# 5VPS.net
KiCad netlist of a schematic drawn in EAGLE
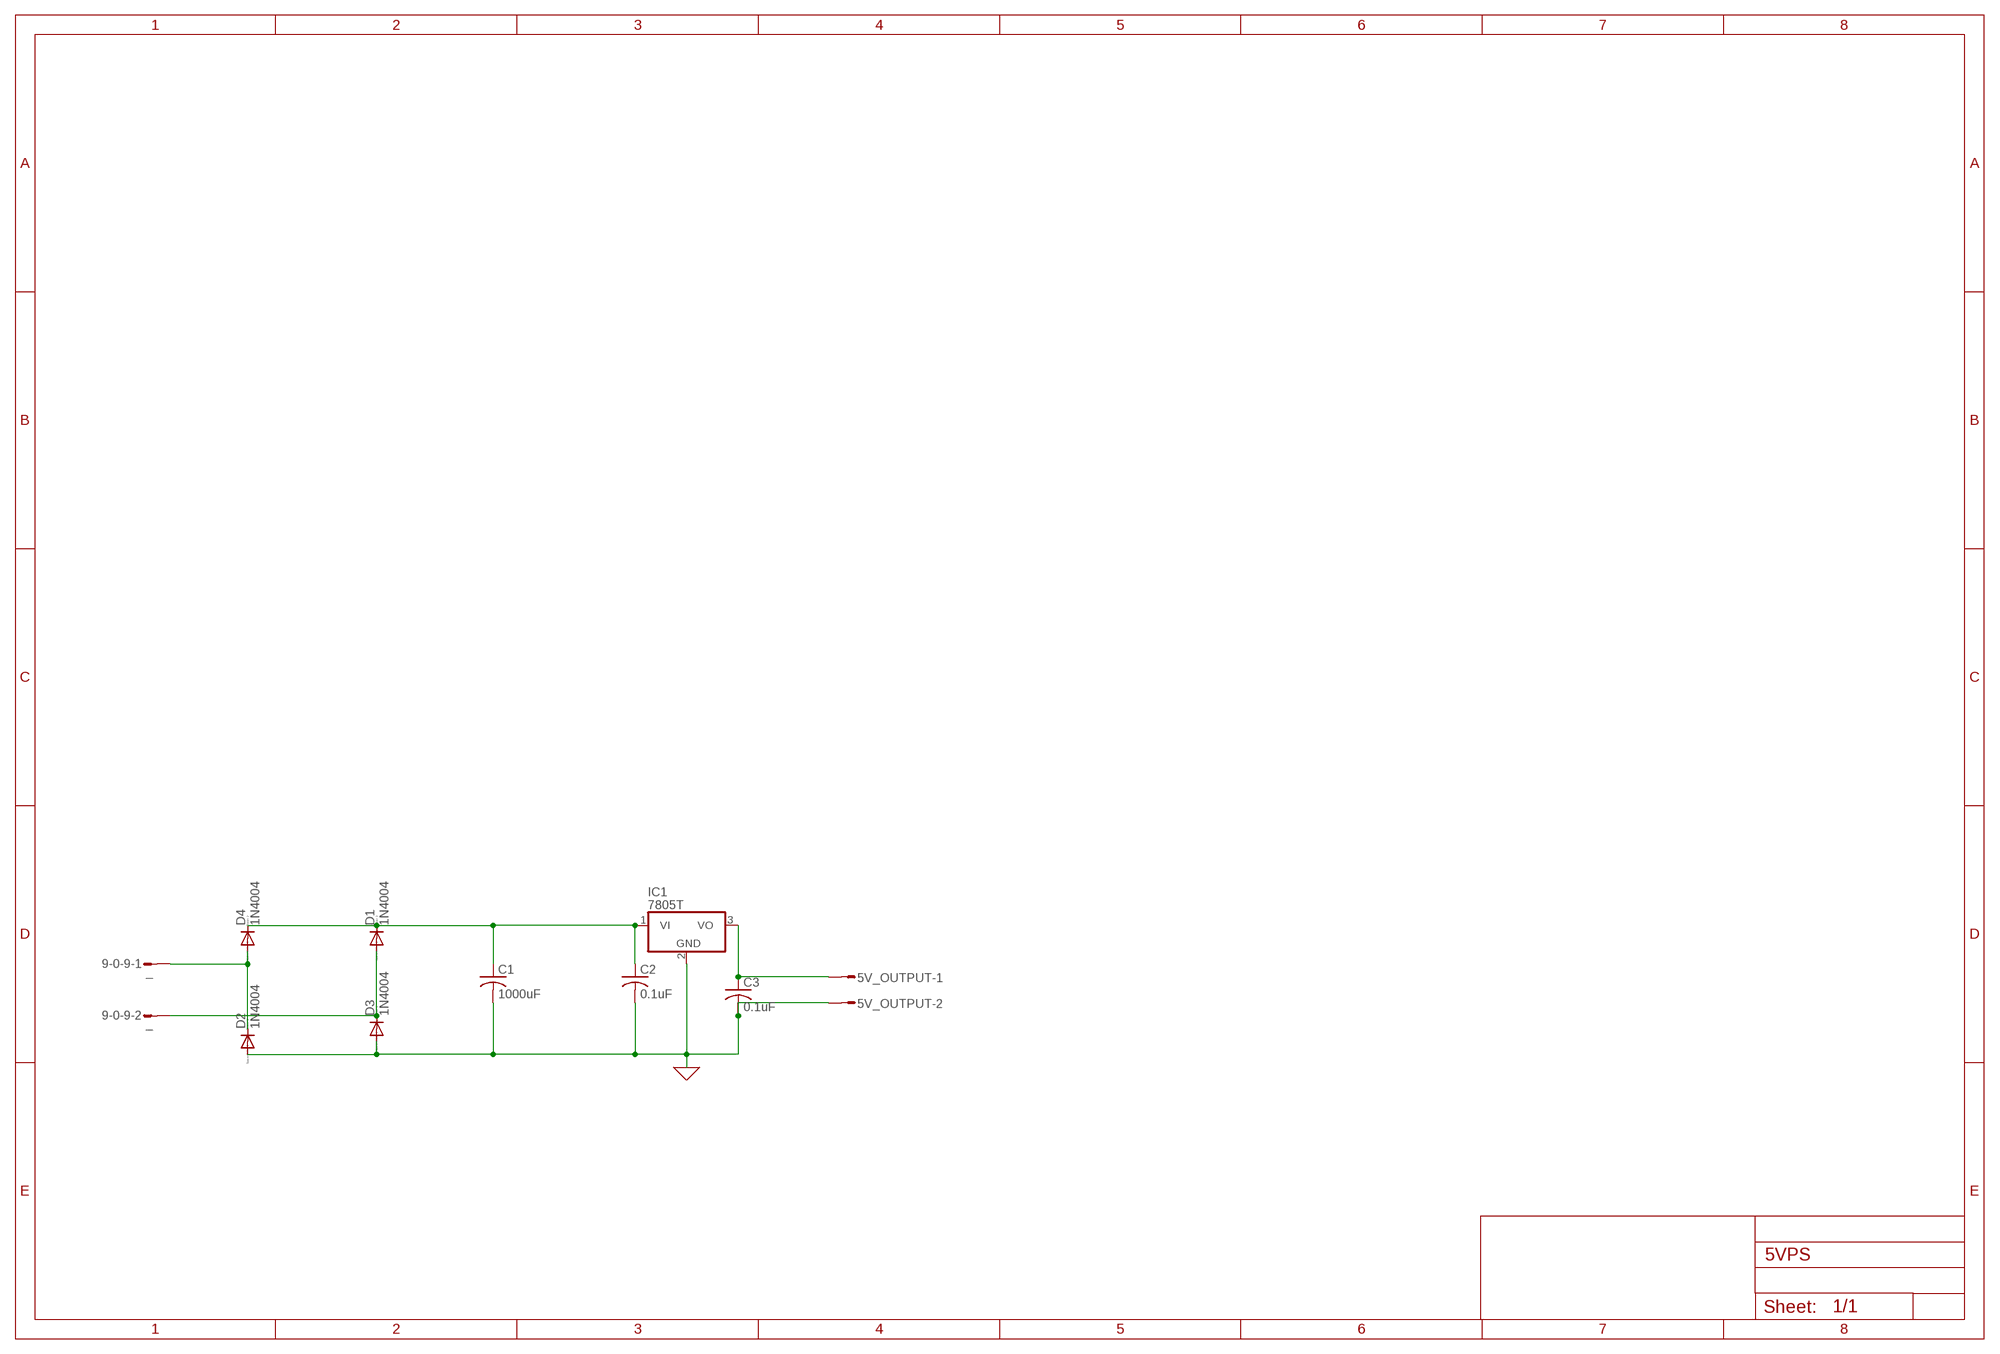
[diagram p0: schematic, sheet 1]

(export (version "E")
  (design (tool "Eeschema 10.0.6"))
  (components
    (comp (ref "5V_OUTPUT")
      (value "L02P")
      (footprint "eagle-import:L02P")
      (libsource (lib "eagle-import") (part "L02P"))
    )
    (comp (ref "9-0-9")
      (value "_")
      (footprint "eagle-import:L02P")
      (libsource (lib "eagle-import") (part "L02P"))
    )
    (comp (ref "C1")
      (value "1000uF")
      (footprint "eagle-import:C025-030X050")
      (libsource (lib "eagle-import") (part "C-US025-030X050"))
    )
    (comp (ref "C2")
      (value "0.1uF")
      (footprint "eagle-import:C025-024X044")
      (libsource (lib "eagle-import") (part "C-US025-024X044"))
    )
    (comp (ref "C3")
      (value "0.1uF")
      (footprint "eagle-import:C025-024X044")
      (libsource (lib "eagle-import") (part "C-US025-024X044"))
    )
    (comp (ref "D1")
      (value "1N4004")
      (footprint "eagle-import:DO41-10")
      (libsource (lib "eagle-import") (part "1N4004"))
    )
    (comp (ref "D2")
      (value "1N4004")
      (footprint "eagle-import:DO41-10")
      (libsource (lib "eagle-import") (part "1N4004"))
    )
    (comp (ref "D3")
      (value "1N4004")
      (footprint "eagle-import:DO41-10")
      (libsource (lib "eagle-import") (part "1N4004"))
    )
    (comp (ref "D4")
      (value "1N4004")
      (footprint "eagle-import:DO41-10")
      (libsource (lib "eagle-import") (part "1N4004"))
    )
    (comp (ref "IC1")
      (value "7805T")
      (footprint "eagle-import:TO220H")
      (libsource (lib "eagle-import") (part "78T05"))
    )
  )
  (nets
    (net (code "1") (name "GND") (class "Default")
      (node (ref "5V_OUTPUT") (pin "2") (pinfunction "S_2") (pintype "passive"))
      (node (ref "C1") (pin "2") (pinfunction "2_2") (pintype "passive"))
      (node (ref "C2") (pin "2") (pinfunction "2_2") (pintype "passive"))
      (node (ref "C3") (pin "2") (pinfunction "2_2") (pintype "passive"))
      (node (ref "D2") (pin "A") (pinfunction "A_A") (pintype "passive"))
      (node (ref "D3") (pin "A") (pinfunction "A_A") (pintype "passive"))
      (node (ref "IC1") (pin "2") (pinfunction "GND_2") (pintype "passive"))
    )
    (net (code "2") (name "Net-(5V_OUTPUTA-S)") (class "Default")
      (node (ref "5V_OUTPUT") (pin "1") (pinfunction "S_1") (pintype "passive"))
      (node (ref "C3") (pin "1") (pinfunction "1_1") (pintype "passive"))
      (node (ref "IC1") (pin "3") (pinfunction "VO_3") (pintype "passive"))
    )
    (net (code "3") (name "Net-(9-0-9A-S)") (class "Default")
      (node (ref "9-0-9") (pin "1") (pinfunction "S_1") (pintype "passive"))
      (node (ref "D2") (pin "C") (pinfunction "C_C") (pintype "passive"))
      (node (ref "D4") (pin "A") (pinfunction "A_A") (pintype "passive"))
    )
    (net (code "4") (name "Net-(9-0-9B-S)") (class "Default")
      (node (ref "9-0-9") (pin "2") (pinfunction "S_2") (pintype "passive"))
      (node (ref "D1") (pin "A") (pinfunction "A_A") (pintype "passive"))
      (node (ref "D3") (pin "C") (pinfunction "C_C") (pintype "passive"))
    )
    (net (code "5") (name "Net-(IC1-VI)") (class "Default")
      (node (ref "C1") (pin "1") (pinfunction "1_1") (pintype "passive"))
      (node (ref "C2") (pin "1") (pinfunction "1_1") (pintype "passive"))
      (node (ref "D1") (pin "C") (pinfunction "C_C") (pintype "passive"))
      (node (ref "D4") (pin "C") (pinfunction "C_C") (pintype "passive"))
      (node (ref "IC1") (pin "1") (pinfunction "VI_1") (pintype "input"))
    )
  )
)
